# Motor_Control_Hat_Schematic.net
KiCad netlist of a schematic drawn in EAGLE
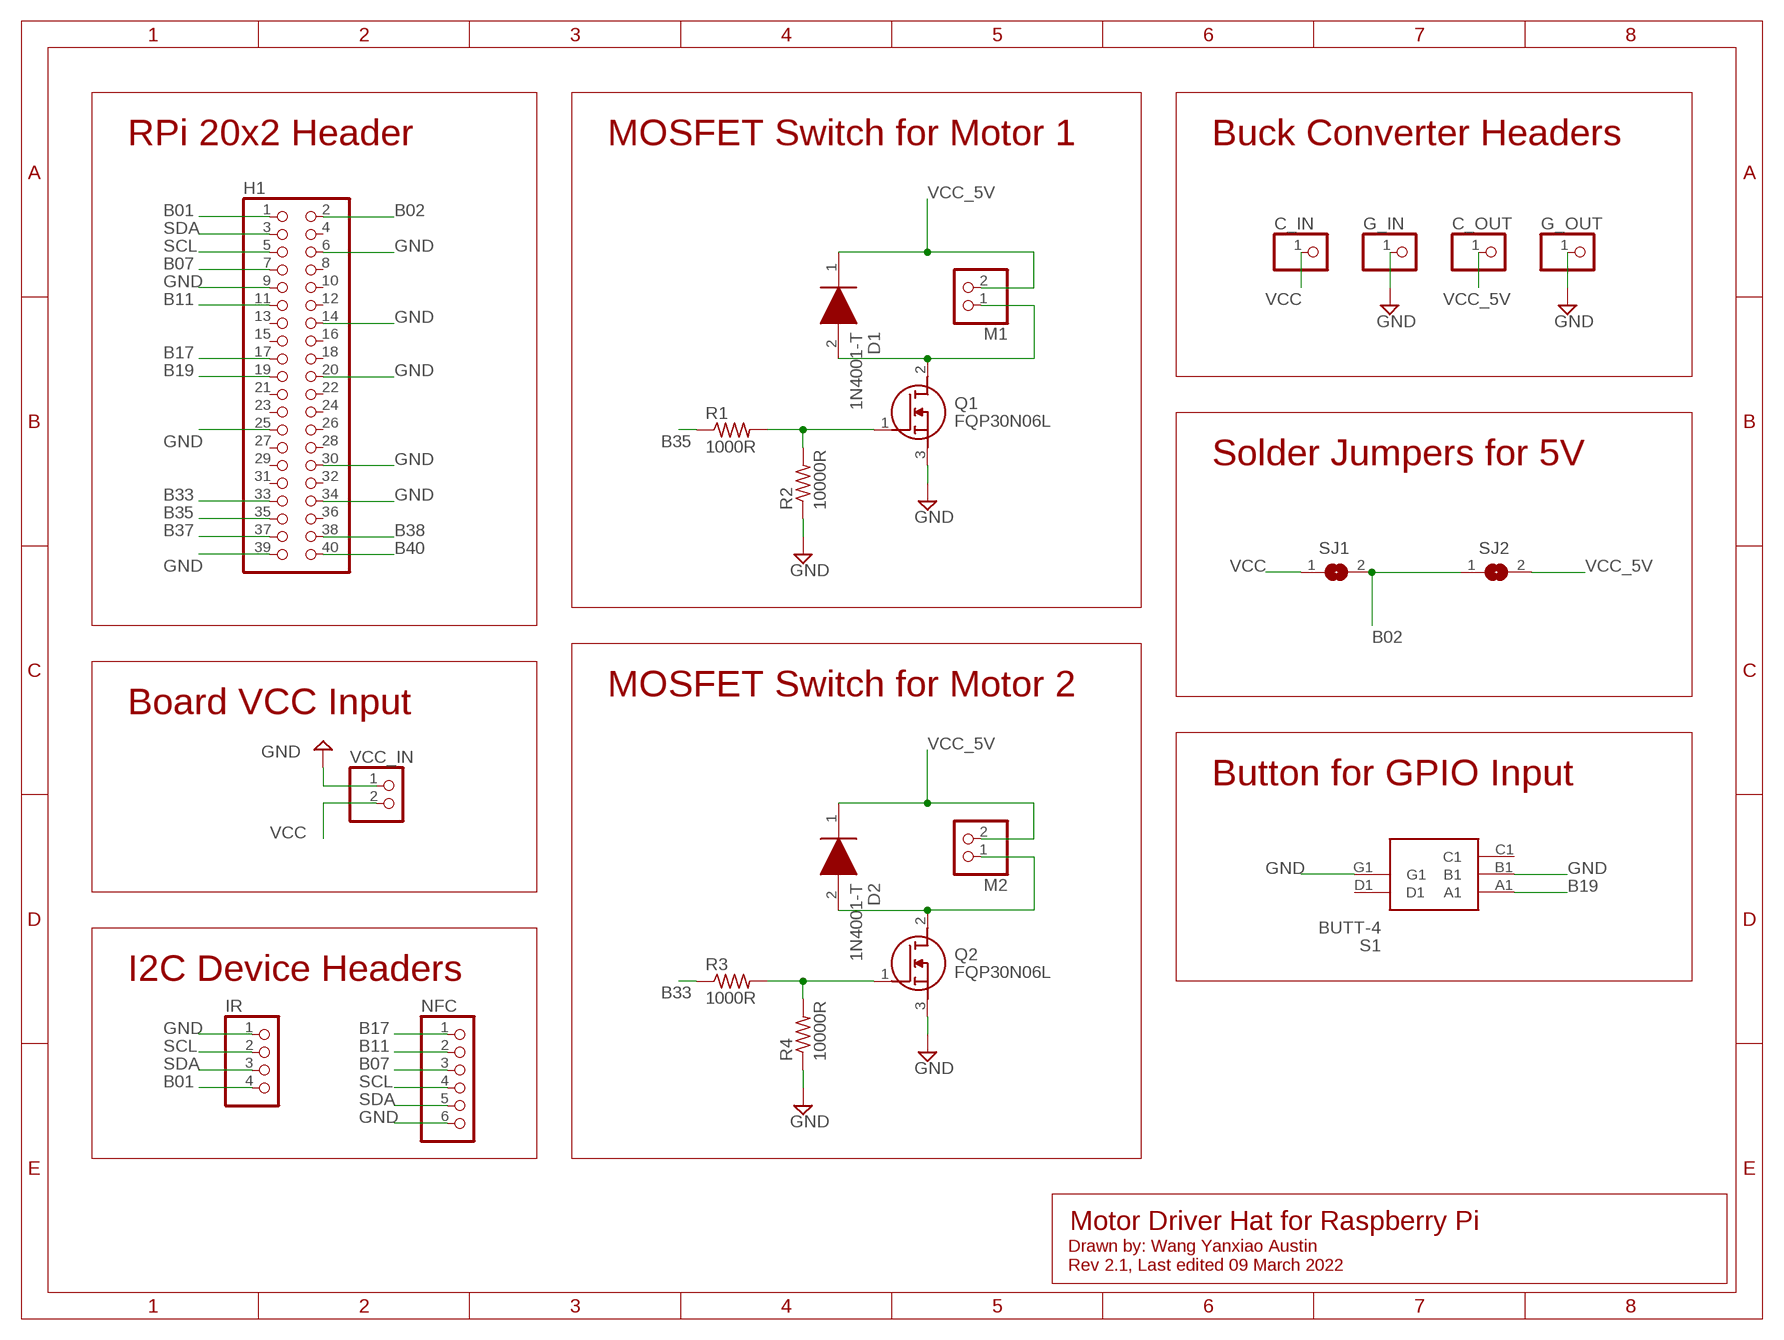
[diagram p0: schematic, sheet 1]
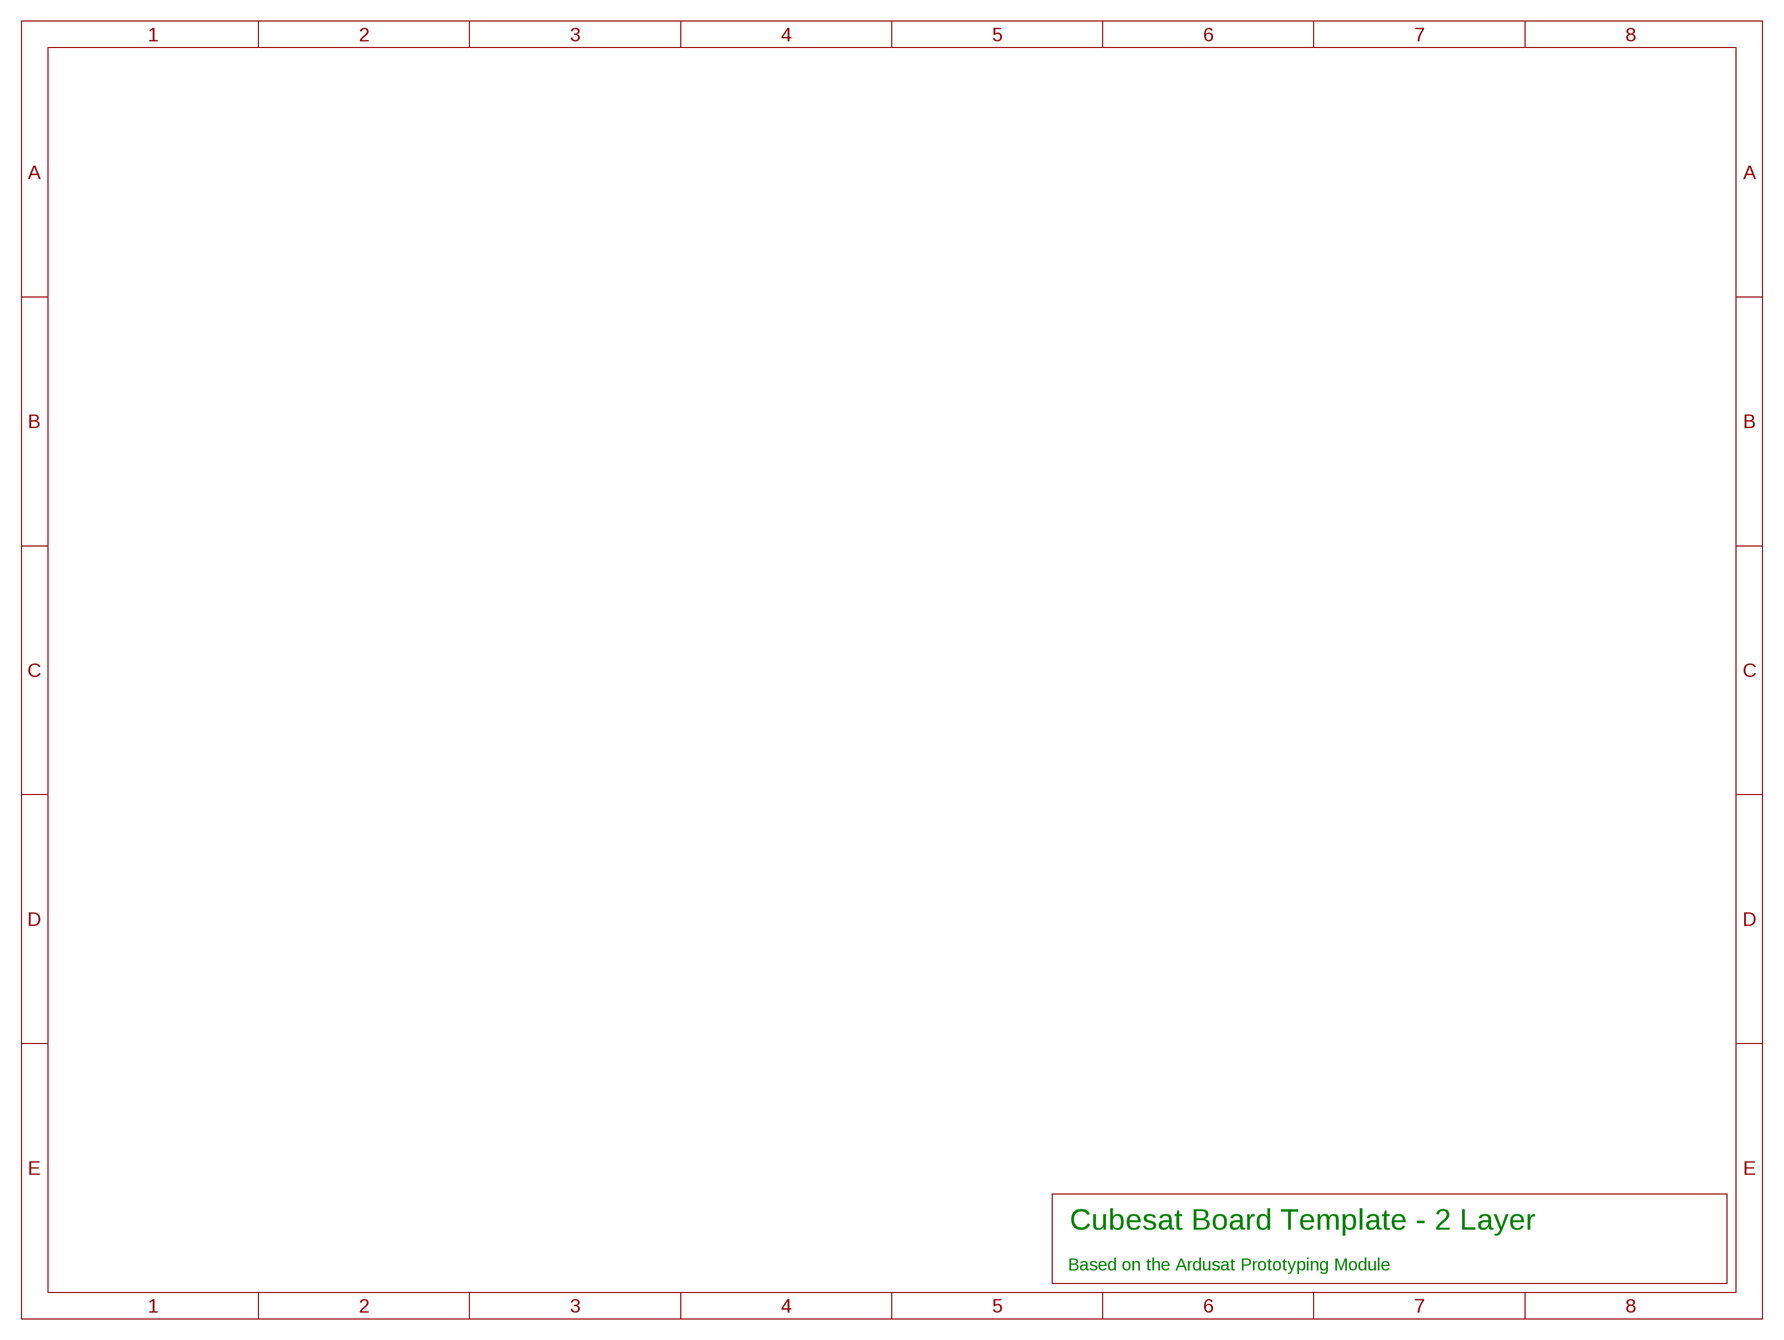
[diagram p1: schematic, sheet 2]

(export (version "E")
  (design (tool "Eeschema 10.0.6"))
  (components
    (comp (ref "C_IN")
      (value "PINHD-1X1")
      (footprint "eagle-import:1X01")
      (libsource (lib "eagle-import") (part "PINHD-1X1"))
    )
    (comp (ref "C_OUT")
      (value "PINHD-1X1")
      (footprint "eagle-import:1X01")
      (libsource (lib "eagle-import") (part "PINHD-1X1"))
    )
    (comp (ref "D1")
      (value "1N4001-T")
      (footprint "eagle-import:DIOAD1408W86L464D236")
      (fields (field (name "MOUSER_PART_NUMBER") "621-1N4001"))
      (libsource (lib "eagle-import") (part "1N4001-T"))
    )
    (comp (ref "D2")
      (value "1N4001-T")
      (footprint "eagle-import:DIOAD1408W86L464D236")
      (fields (field (name "MOUSER_PART_NUMBER") "621-1N4001"))
      (libsource (lib "eagle-import") (part "1N4001-T"))
    )
    (comp (ref "G_IN")
      (value "PINHD-1X1")
      (footprint "eagle-import:1X01")
      (libsource (lib "eagle-import") (part "PINHD-1X1"))
    )
    (comp (ref "G_OUT")
      (value "PINHD-1X1")
      (footprint "eagle-import:1X01")
      (libsource (lib "eagle-import") (part "PINHD-1X1"))
    )
    (comp (ref "H1")
      (value "PINHD-2X20")
      (footprint "eagle-import:2X20")
      (fields (field (name "SPICEPREFIX") "X"))
      (libsource (lib "eagle-import") (part "PINHD-2X20"))
    )
    (comp (ref "IR")
      (value "PINHD-1X4")
      (footprint "eagle-import:1X04")
      (libsource (lib "eagle-import") (part "PINHD-1X4"))
    )
    (comp (ref "M1")
      (value "PINHD-1X2")
      (footprint "eagle-import:1X02")
      (libsource (lib "eagle-import") (part "PINHD-1X2"))
    )
    (comp (ref "M2")
      (value "PINHD-1X2")
      (footprint "eagle-import:1X02")
      (libsource (lib "eagle-import") (part "PINHD-1X2"))
    )
    (comp (ref "NFC")
      (value "PINHD-1X6")
      (footprint "eagle-import:1X06")
      (libsource (lib "eagle-import") (part "PINHD-1X6"))
    )
    (comp (ref "Q1")
      (value "FQP30N06L")
      (footprint "eagle-import:TO254P470X1016X2019-3P")
      (fields (field (name "MOUSER_PART_NUMBER") "512-FQP30N06L"))
      (libsource (lib "eagle-import") (part "FQP30N06L"))
    )
    (comp (ref "Q2")
      (value "FQP30N06L")
      (footprint "eagle-import:TO254P470X1016X2019-3P")
      (fields (field (name "MOUSER_PART_NUMBER") "512-FQP30N06L"))
      (libsource (lib "eagle-import") (part "FQP30N06L"))
    )
    (comp (ref "R1")
      (value "1000R")
      (footprint "eagle-import:0207_10")
      (libsource (lib "eagle-import") (part "R-US_0207/10"))
    )
    (comp (ref "R2")
      (value "10000R")
      (footprint "eagle-import:0207_10")
      (libsource (lib "eagle-import") (part "R-US_0207/10"))
    )
    (comp (ref "R3")
      (value "1000R")
      (footprint "eagle-import:0207_10")
      (libsource (lib "eagle-import") (part "R-US_0207/10"))
    )
    (comp (ref "R4")
      (value "10000R")
      (footprint "eagle-import:0207_10")
      (libsource (lib "eagle-import") (part "R-US_0207/10"))
    )
    (comp (ref "S1")
      (value "BUTT-4")
      (footprint "eagle-import:BUTT4")
      (fields (field (name "MOUSER_PART_NUMBER") "992-BUTT-4"))
      (libsource (lib "eagle-import") (part "BUTT-4"))
    )
    (comp (ref "SJ1") (value "SJ") (footprint "eagle-import:SJ") (libsource (lib "eagle-import") (part "SJ")))
    (comp (ref "SJ2") (value "SJ") (footprint "eagle-import:SJ") (libsource (lib "eagle-import") (part "SJ")))
    (comp (ref "VCC_IN")
      (value "PINHD-1X2")
      (footprint "eagle-import:1X02")
      (libsource (lib "eagle-import") (part "PINHD-1X2"))
    )
  )
  (nets
    (net (code "1") (name "B01") (class "Default")
      (node (ref "H1") (pin "1") (pinfunction "1_1") (pintype "passive"))
      (node (ref "IR") (pin "4") (pinfunction "4_4") (pintype "passive"))
    )
    (net (code "2") (name "B02") (class "Default")
      (node (ref "H1") (pin "2") (pinfunction "2_2") (pintype "passive"))
      (node (ref "SJ1") (pin "2") (pinfunction "2_2") (pintype "passive"))
      (node (ref "SJ2") (pin "1") (pinfunction "1_1") (pintype "passive"))
    )
    (net (code "3") (name "B07") (class "Default")
      (node (ref "H1") (pin "7") (pinfunction "7_7") (pintype "passive"))
      (node (ref "NFC") (pin "3") (pinfunction "3_3") (pintype "passive"))
    )
    (net (code "4") (name "B11") (class "Default")
      (node (ref "H1") (pin "11") (pinfunction "11_11") (pintype "passive"))
      (node (ref "NFC") (pin "2") (pinfunction "2_2") (pintype "passive"))
    )
    (net (code "5") (name "B17") (class "Default")
      (node (ref "H1") (pin "17") (pinfunction "17_17") (pintype "passive"))
      (node (ref "NFC") (pin "1") (pinfunction "1_1") (pintype "passive"))
    )
    (net (code "6") (name "B19") (class "Default")
      (node (ref "H1") (pin "19") (pinfunction "19_19") (pintype "passive"))
      (node (ref "S1") (pin "A1") (pinfunction "A1_A1") (pintype "bidirectional"))
    )
    (net (code "7") (name "B33") (class "Default")
      (node (ref "H1") (pin "33") (pinfunction "33_33") (pintype "passive"))
      (node (ref "R3") (pin "1") (pinfunction "1_1") (pintype "passive"))
    )
    (net (code "8") (name "B35") (class "Default")
      (node (ref "H1") (pin "35") (pinfunction "35_35") (pintype "passive"))
      (node (ref "R1") (pin "1") (pinfunction "1_1") (pintype "passive"))
    )
    (net (code "9") (name "B37") (class "Default")
      (node (ref "H1") (pin "37") (pinfunction "37_37") (pintype "passive"))
    )
    (net (code "10") (name "B38") (class "Default")
      (node (ref "H1") (pin "38") (pinfunction "38_38") (pintype "passive"))
    )
    (net (code "11") (name "B40") (class "Default")
      (node (ref "H1") (pin "40") (pinfunction "40_40") (pintype "passive"))
    )
    (net (code "12") (name "GND") (class "Default")
      (node (ref "G_IN") (pin "1") (pinfunction "1_1") (pintype "passive"))
      (node (ref "G_OUT") (pin "1") (pinfunction "1_1") (pintype "passive"))
      (node (ref "H1") (pin "14") (pinfunction "14_14") (pintype "passive"))
      (node (ref "H1") (pin "20") (pinfunction "20_20") (pintype "passive"))
      (node (ref "H1") (pin "25") (pinfunction "25_25") (pintype "passive"))
      (node (ref "H1") (pin "30") (pinfunction "30_30") (pintype "passive"))
      (node (ref "H1") (pin "34") (pinfunction "34_34") (pintype "passive"))
      (node (ref "H1") (pin "39") (pinfunction "39_39") (pintype "passive"))
      (node (ref "H1") (pin "6") (pinfunction "6_6") (pintype "passive"))
      (node (ref "H1") (pin "9") (pinfunction "9_9") (pintype "passive"))
      (node (ref "IR") (pin "1") (pinfunction "1_1") (pintype "passive"))
      (node (ref "NFC") (pin "6") (pinfunction "6_6") (pintype "passive"))
      (node (ref "Q1") (pin "3") (pinfunction "S_3") (pintype "bidirectional"))
      (node (ref "Q2") (pin "3") (pinfunction "S_3") (pintype "bidirectional"))
      (node (ref "R2") (pin "1") (pinfunction "1_1") (pintype "passive"))
      (node (ref "R4") (pin "1") (pinfunction "1_1") (pintype "passive"))
      (node (ref "S1") (pin "B1") (pinfunction "B1_B1") (pintype "bidirectional"))
      (node (ref "S1") (pin "G1") (pinfunction "G1_G1") (pintype "bidirectional"))
      (node (ref "VCC_IN") (pin "1") (pinfunction "1_1") (pintype "passive"))
    )
    (net (code "13") (name "Net-(D1-A)") (class "Default")
      (node (ref "D1") (pin "2") (pinfunction "A_2") (pintype "bidirectional"))
      (node (ref "M1") (pin "1") (pinfunction "1_1") (pintype "passive"))
      (node (ref "Q1") (pin "2") (pinfunction "D_2") (pintype "bidirectional"))
    )
    (net (code "14") (name "Net-(D2-A)") (class "Default")
      (node (ref "D2") (pin "2") (pinfunction "A_2") (pintype "bidirectional"))
      (node (ref "M2") (pin "1") (pinfunction "1_1") (pintype "passive"))
      (node (ref "Q2") (pin "2") (pinfunction "D_2") (pintype "bidirectional"))
    )
    (net (code "15") (name "Net-(Q1-G)") (class "Default")
      (node (ref "Q1") (pin "1") (pinfunction "G_1") (pintype "bidirectional"))
      (node (ref "R1") (pin "2") (pinfunction "2_2") (pintype "passive"))
      (node (ref "R2") (pin "2") (pinfunction "2_2") (pintype "passive"))
    )
    (net (code "16") (name "Net-(Q2-G)") (class "Default")
      (node (ref "Q2") (pin "1") (pinfunction "G_1") (pintype "bidirectional"))
      (node (ref "R3") (pin "2") (pinfunction "2_2") (pintype "passive"))
      (node (ref "R4") (pin "2") (pinfunction "2_2") (pintype "passive"))
    )
    (net (code "17") (name "SCL") (class "Default")
      (node (ref "H1") (pin "5") (pinfunction "5_5") (pintype "passive"))
      (node (ref "IR") (pin "2") (pinfunction "2_2") (pintype "passive"))
      (node (ref "NFC") (pin "4") (pinfunction "4_4") (pintype "passive"))
    )
    (net (code "18") (name "SDA") (class "Default")
      (node (ref "H1") (pin "3") (pinfunction "3_3") (pintype "passive"))
      (node (ref "IR") (pin "3") (pinfunction "3_3") (pintype "passive"))
      (node (ref "NFC") (pin "5") (pinfunction "5_5") (pintype "passive"))
    )
    (net (code "19") (name "VCC") (class "Default")
      (node (ref "C_IN") (pin "1") (pinfunction "1_1") (pintype "passive"))
      (node (ref "SJ1") (pin "1") (pinfunction "1_1") (pintype "passive"))
      (node (ref "VCC_IN") (pin "2") (pinfunction "2_2") (pintype "passive"))
    )
    (net (code "20") (name "VCC_5V") (class "Default")
      (node (ref "C_OUT") (pin "1") (pinfunction "1_1") (pintype "passive"))
      (node (ref "D1") (pin "1") (pinfunction "K_1") (pintype "bidirectional"))
      (node (ref "D2") (pin "1") (pinfunction "K_1") (pintype "bidirectional"))
      (node (ref "M1") (pin "2") (pinfunction "2_2") (pintype "passive"))
      (node (ref "M2") (pin "2") (pinfunction "2_2") (pintype "passive"))
      (node (ref "SJ2") (pin "2") (pinfunction "2_2") (pintype "passive"))
    )
    (net (code "21") (name "unconnected-(H1-Pad4)") (class "Default")
      (node (ref "H1") (pin "4") (pinfunction "4_4") (pintype "passive"))
    )
    (net (code "22") (name "unconnected-(H1-Pad8)") (class "Default")
      (node (ref "H1") (pin "8") (pinfunction "8_8") (pintype "passive"))
    )
    (net (code "23") (name "unconnected-(H1-Pad10)") (class "Default")
      (node (ref "H1") (pin "10") (pinfunction "10_10") (pintype "passive"))
    )
    (net (code "24") (name "unconnected-(H1-Pad12)") (class "Default")
      (node (ref "H1") (pin "12") (pinfunction "12_12") (pintype "passive"))
    )
    (net (code "25") (name "unconnected-(H1-Pad13)") (class "Default")
      (node (ref "H1") (pin "13") (pinfunction "13_13") (pintype "passive"))
    )
    (net (code "26") (name "unconnected-(H1-Pad15)") (class "Default")
      (node (ref "H1") (pin "15") (pinfunction "15_15") (pintype "passive"))
    )
    (net (code "27") (name "unconnected-(H1-Pad16)") (class "Default")
      (node (ref "H1") (pin "16") (pinfunction "16_16") (pintype "passive"))
    )
    (net (code "28") (name "unconnected-(H1-Pad18)") (class "Default")
      (node (ref "H1") (pin "18") (pinfunction "18_18") (pintype "passive"))
    )
    (net (code "29") (name "unconnected-(H1-Pad21)") (class "Default")
      (node (ref "H1") (pin "21") (pinfunction "21_21") (pintype "passive"))
    )
    (net (code "30") (name "unconnected-(H1-Pad22)") (class "Default")
      (node (ref "H1") (pin "22") (pinfunction "22_22") (pintype "passive"))
    )
    (net (code "31") (name "unconnected-(H1-Pad23)") (class "Default")
      (node (ref "H1") (pin "23") (pinfunction "23_23") (pintype "passive"))
    )
    (net (code "32") (name "unconnected-(H1-Pad24)") (class "Default")
      (node (ref "H1") (pin "24") (pinfunction "24_24") (pintype "passive"))
    )
    (net (code "33") (name "unconnected-(H1-Pad26)") (class "Default")
      (node (ref "H1") (pin "26") (pinfunction "26_26") (pintype "passive"))
    )
    (net (code "34") (name "unconnected-(H1-Pad27)") (class "Default")
      (node (ref "H1") (pin "27") (pinfunction "27_27") (pintype "passive"))
    )
    (net (code "35") (name "unconnected-(H1-Pad28)") (class "Default")
      (node (ref "H1") (pin "28") (pinfunction "28_28") (pintype "passive"))
    )
    (net (code "36") (name "unconnected-(H1-Pad29)") (class "Default")
      (node (ref "H1") (pin "29") (pinfunction "29_29") (pintype "passive"))
    )
    (net (code "37") (name "unconnected-(H1-Pad31)") (class "Default")
      (node (ref "H1") (pin "31") (pinfunction "31_31") (pintype "passive"))
    )
    (net (code "38") (name "unconnected-(H1-Pad32)") (class "Default")
      (node (ref "H1") (pin "32") (pinfunction "32_32") (pintype "passive"))
    )
    (net (code "39") (name "unconnected-(H1-Pad36)") (class "Default")
      (node (ref "H1") (pin "36") (pinfunction "36_36") (pintype "passive"))
    )
    (net (code "40") (name "unconnected-(S1-PadC1)") (class "Default")
      (node (ref "S1") (pin "C1") (pinfunction "C1_C1") (pintype "bidirectional"))
    )
    (net (code "41") (name "unconnected-(S1-PadD1)") (class "Default")
      (node (ref "S1") (pin "D1") (pinfunction "D1_D1") (pintype "bidirectional"))
    )
  )
)
